# GPS.net
KiCad netlist of a schematic drawn in Altium Designer
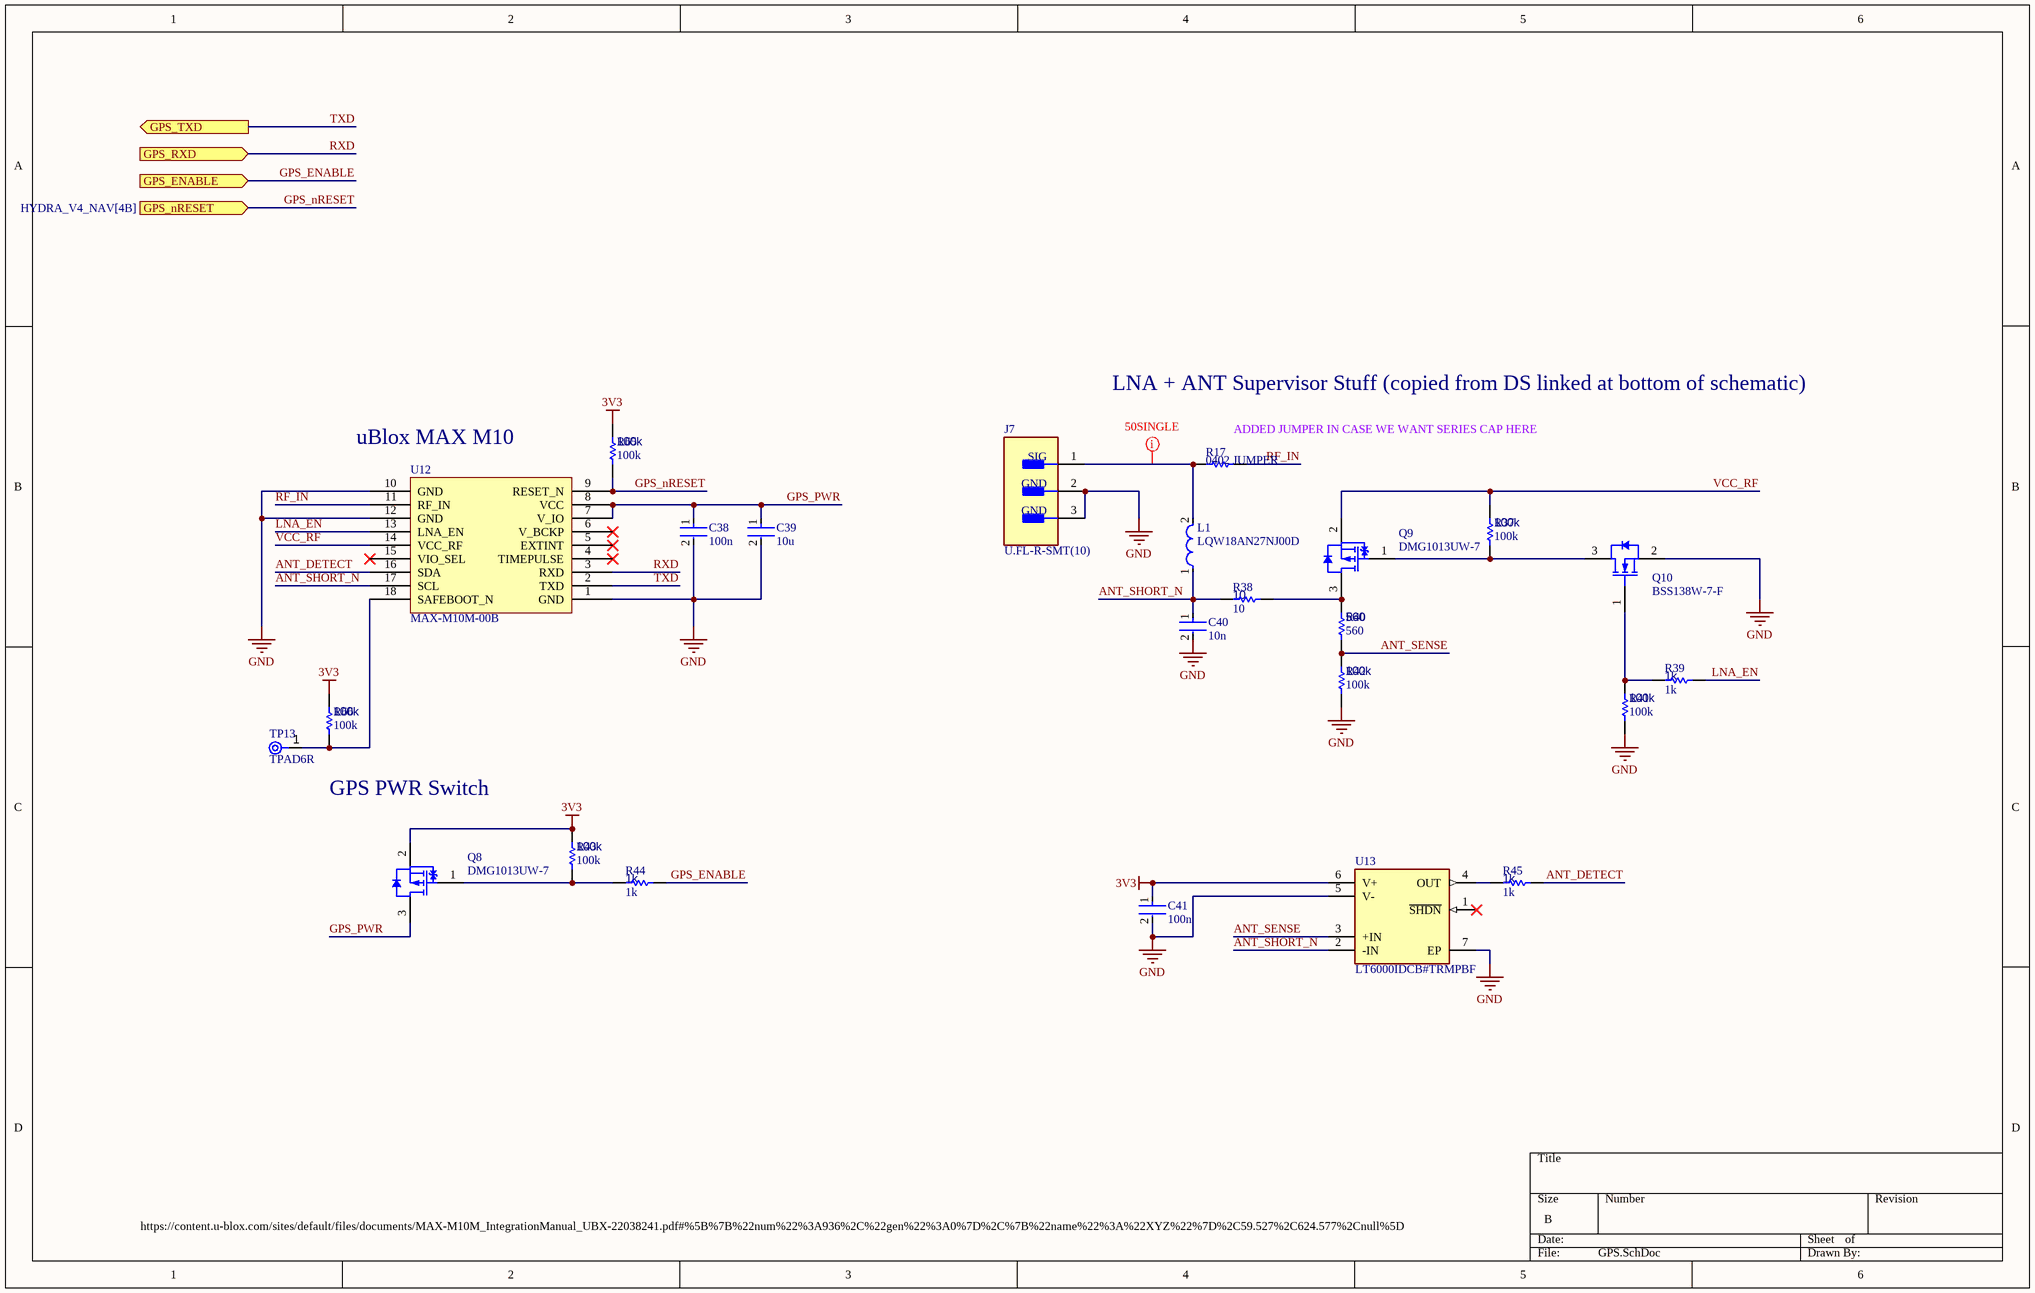
[diagram p0: GPS.SchDoc]

(export (version "E")
  (design (tool "Eeschema 10.0.6"))
  (components
    (comp (ref "C38")
      (value "100n")
      (footprint "FP-0402-L_1_0_0_05-W_0_5-IPC_A")
      (description "LARGE PADS, 0402 CAP, CHANGE COMMENT TO MATCH REAL P/N")
      (libsource (lib "Space Concordia") (part "b4654b650e69147ec39a6b967a45e02"))
    )
    (comp (ref "C39")
      (value "10u")
      (footprint "FP-0402-L_1_0_0_05-W_0_5-IPC_A")
      (description "LARGE PADS, 0402 CAP, CHANGE COMMENT TO MATCH REAL P/N")
      (libsource (lib "Space Concordia") (part "b4654b650e69147ec39a6b967a45e02"))
    )
    (comp (ref "C40")
      (value "10n")
      (footprint "FP-0402-L_1_0_0_05-W_0_5-IPC_A")
      (description "LARGE PADS, 0402 CAP, CHANGE COMMENT TO MATCH REAL P/N")
      (libsource (lib "Space Concordia") (part "b4654b650e69147ec39a6b967a45e02"))
    )
    (comp (ref "C41")
      (value "100n")
      (footprint "FP-0402-L_1_0_0_05-W_0_5-IPC_A")
      (description "LARGE PADS, 0402 CAP, CHANGE COMMENT TO MATCH REAL P/N")
      (libsource (lib "Space Concordia") (part "b4654b650e69147ec39a6b967a45e02"))
    )
    (comp (ref "J7")
      (value "U.FL-R-SMT(10)")
      (footprint "FP-U_FL-R-SMT_10-MFG")
      (description "CONN U.FL RCPT STR 50 OHM SMD")
      (libsource (lib "Altium Content Vault") (part "eef6fde44c591823e8076210edfe12f"))
    )
    (comp (ref "L1")
      (value "LQW18AN27NJ00D")
      (footprint "FP-LQW18AN_00-MFG")
      (description "Wire Wound RF Inductor 27nH ±5% 440mA 0.21Ω 0603 (1608)")
      (fields (field (name "TOLERANCE") "5%"))
      (libsource (lib "Altium Content Vault") (part "725321dda6339637d4d059423bc1c3c"))
    )
    (comp (ref "Q8")
      (value "DMG1013UW-7")
      (footprint "DIOD-SOT323-3_V")
      (fields (field (name "MANUFACTURER") "Diodes Inc"))
      (libsource (lib "Altium Content Vault") (part "PEMOS-GSD-3_C"))
    )
    (comp (ref "Q9")
      (value "DMG1013UW-7")
      (footprint "DIOD-SOT323-3_V")
      (fields (field (name "MANUFACTURER") "Diodes Inc"))
      (libsource (lib "Altium Content Vault") (part "PEMOS-GSD-3_C"))
    )
    (comp (ref "Q10")
      (value "BSS138W-7-F")
      (footprint "DIOD-SOT323-3_V")
      (fields (field (name "MANUFACTURER") "DiodesIncorporated"))
      (libsource (lib "Altium Content Vault") (part "NEMOS-GSD-3"))
    )
    (comp (ref "R17")
      (value "0402 JUMPER")
      (footprint "RESC1005X40X25ML05T05")
      (description "READ THE NAME")
      (libsource (lib "Space Concordia") (part "CMP-009-00206-2"))
    )
    (comp (ref "R37")
      (value "100k")
      (footprint "R0603B")
      (description "Resistor")
      (fields (field (name "ALTIUM_VALUE") "100k"))
      (libsource (lib "Space Concordia") (part "Resistor"))
    )
    (comp (ref "R38")
      (value "10")
      (footprint "R0603B")
      (description "Resistor")
      (fields (field (name "ALTIUM_VALUE") "10"))
      (libsource (lib "Space Concordia") (part "Resistor"))
    )
    (comp (ref "R39")
      (value "1k")
      (footprint "R0603B")
      (description "Resistor")
      (fields (field (name "ALTIUM_VALUE") "1k"))
      (libsource (lib "Space Concordia") (part "Resistor"))
    )
    (comp (ref "R40")
      (value "560")
      (footprint "R0603B")
      (description "Resistor")
      (fields (field (name "ALTIUM_VALUE") "560"))
      (libsource (lib "Space Concordia") (part "Resistor"))
    )
    (comp (ref "R41")
      (value "100k")
      (footprint "R0603B")
      (description "Resistor")
      (fields (field (name "ALTIUM_VALUE") "100k"))
      (libsource (lib "Space Concordia") (part "Resistor"))
    )
    (comp (ref "R42")
      (value "100k")
      (footprint "R0603B")
      (description "Resistor")
      (fields (field (name "ALTIUM_VALUE") "100k"))
      (libsource (lib "Space Concordia") (part "Resistor"))
    )
    (comp (ref "R43")
      (value "100k")
      (footprint "R0603B")
      (description "Resistor")
      (fields (field (name "ALTIUM_VALUE") "100k"))
      (libsource (lib "Space Concordia") (part "Resistor"))
    )
    (comp (ref "R44")
      (value "1k")
      (footprint "R0603B")
      (description "Resistor")
      (fields (field (name "ALTIUM_VALUE") "1k"))
      (libsource (lib "Space Concordia") (part "Resistor"))
    )
    (comp (ref "R45")
      (value "1k")
      (footprint "R0603B")
      (description "Resistor")
      (fields (field (name "ALTIUM_VALUE") "1k"))
      (libsource (lib "Space Concordia") (part "Resistor"))
    )
    (comp (ref "R65")
      (value "100k")
      (footprint "R0603B")
      (description "Resistor")
      (fields (field (name "ALTIUM_VALUE") "100k"))
      (libsource (lib "Space Concordia") (part "Resistor"))
    )
    (comp (ref "R66")
      (value "100k")
      (footprint "R0603B")
      (description "Resistor")
      (fields (field (name "ALTIUM_VALUE") "100k"))
      (libsource (lib "Space Concordia") (part "Resistor"))
    )
    (comp (ref "TP13")
      (value "TPAD6R")
      (footprint "New footprint 1")
      (description "Test Point .6mm")
      (libsource (lib "Space Concordia") (part "TP"))
    )
    (comp (ref "U12")
      (value "MAX-M10M-00B")
      (footprint "MAX-M10M-00B-Footprint-1")
      (description "Gnss Lcc Rx Mod, Rom, Crystal")
      (libsource (lib "Space Concordia") (part "MAX-M10M-00B"))
    )
    (comp (ref "U13")
      (value "LT6000IDCB#TRMPBF")
      (footprint "FP-DCB-6-05-08-1715-MFG")
      (description "IC OPAMP GP 1 CIRCUIT 6DFN")
      (libsource (lib "Altium Content Vault") (part "33bb285994f2e703f79bf9d86341a8a"))
    )
  )
  (nets
    (net (code "1") (name "/ANT_DETECT") (class "Default")
      (node (ref "R45") (pin "2") (pinfunction "2_2") (pintype "passive"))
      (node (ref "U12") (pin "16") (pinfunction "SDA_16") (pintype "passive"))
    )
    (net (code "2") (name "/ANT_SENSE") (class "Default")
      (node (ref "R40") (pin "2") (pinfunction "2_2") (pintype "passive"))
      (node (ref "R42") (pin "1") (pinfunction "1_1") (pintype "passive"))
      (node (ref "U13") (pin "3") (pinfunction "+IN_3") (pintype "tri_state"))
    )
    (net (code "3") (name "/ANT_SHORT_N") (class "Default")
      (node (ref "C40") (pin "1") (pinfunction "1_1") (pintype "passive"))
      (node (ref "L1") (pin "1") (pinfunction "1_1") (pintype "passive"))
      (node (ref "R38") (pin "1") (pinfunction "1_1") (pintype "passive"))
      (node (ref "U12") (pin "17") (pinfunction "SCL_17") (pintype "passive"))
      (node (ref "U13") (pin "2") (pinfunction "-IN_2") (pintype "tri_state"))
    )
    (net (code "4") (name "/GPS_ENABLE") (class "Default")
      (node (ref "R44") (pin "2") (pinfunction "2_2") (pintype "passive"))
    )
    (net (code "5") (name "/GPS_PWR") (class "Default")
      (node (ref "C38") (pin "1") (pinfunction "1_1") (pintype "passive"))
      (node (ref "C39") (pin "1") (pinfunction "1_1") (pintype "passive"))
      (node (ref "Q8") (pin "3") (pinfunction "D_3") (pintype "passive"))
      (node (ref "U12") (pin "7") (pinfunction "V_IO_7") (pintype "passive"))
      (node (ref "U12") (pin "8") (pinfunction "VCC_8") (pintype "passive"))
    )
    (net (code "6") (name "/GPS_nRESET") (class "Default")
      (node (ref "R65") (pin "2") (pinfunction "2_2") (pintype "passive"))
      (node (ref "U12") (pin "9") (pinfunction "RESET_N_9") (pintype "passive"))
    )
    (net (code "7") (name "/LNA_EN") (class "Default")
      (node (ref "R39") (pin "2") (pinfunction "2_2") (pintype "passive"))
      (node (ref "U12") (pin "13") (pinfunction "LNA_EN_13") (pintype "passive"))
    )
    (net (code "8") (name "/RF_IN") (class "Default")
      (node (ref "R17") (pin "2") (pinfunction "2_2") (pintype "passive"))
      (node (ref "U12") (pin "11") (pinfunction "RF_IN_11") (pintype "passive"))
    )
    (net (code "9") (name "/RXD") (class "Default")
      (node (ref "U12") (pin "3") (pinfunction "RXD_3") (pintype "passive"))
    )
    (net (code "10") (name "/TXD") (class "Default")
      (node (ref "U12") (pin "2") (pinfunction "TXD_2") (pintype "passive"))
    )
    (net (code "11") (name "/VCC_RF") (class "Default")
      (node (ref "Q9") (pin "2") (pinfunction "S_2") (pintype "passive"))
      (node (ref "R37") (pin "1") (pinfunction "1_1") (pintype "passive"))
      (node (ref "U12") (pin "14") (pinfunction "VCC_RF_14") (pintype "passive"))
    )
    (net (code "12") (name "3V3") (class "Default")
      (node (ref "C41") (pin "1") (pinfunction "1_1") (pintype "passive"))
      (node (ref "Q8") (pin "2") (pinfunction "S_2") (pintype "passive"))
      (node (ref "R43") (pin "1") (pinfunction "1_1") (pintype "passive"))
      (node (ref "R65") (pin "1") (pinfunction "1_1") (pintype "passive"))
      (node (ref "R66") (pin "1") (pinfunction "1_1") (pintype "passive"))
      (node (ref "U13") (pin "6") (pinfunction "V+_6") (pintype "power_in"))
    )
    (net (code "13") (name "GND") (class "Default")
      (node (ref "C38") (pin "2") (pinfunction "2_2") (pintype "passive"))
      (node (ref "C39") (pin "2") (pinfunction "2_2") (pintype "passive"))
      (node (ref "C40") (pin "2") (pinfunction "2_2") (pintype "passive"))
      (node (ref "C41") (pin "2") (pinfunction "2_2") (pintype "passive"))
      (node (ref "J7") (pin "2") (pinfunction "GND_2") (pintype "power_in"))
      (node (ref "J7") (pin "3") (pinfunction "GND_3") (pintype "power_in"))
      (node (ref "Q10") (pin "2") (pinfunction "S_2") (pintype "passive"))
      (node (ref "R41") (pin "2") (pinfunction "2_2") (pintype "passive"))
      (node (ref "R42") (pin "2") (pinfunction "2_2") (pintype "passive"))
      (node (ref "U12") (pin "1") (pinfunction "GND_1") (pintype "passive"))
      (node (ref "U12") (pin "10") (pinfunction "GND_10") (pintype "passive"))
      (node (ref "U12") (pin "12") (pinfunction "GND_12") (pintype "passive"))
      (node (ref "U13") (pin "5") (pinfunction "V-_5") (pintype "power_in"))
      (node (ref "U13") (pin "7") (pinfunction "EP_7") (pintype "power_in"))
    )
    (net (code "14") (name "Net-(J7-SIG)") (class "Default")
      (node (ref "J7") (pin "1") (pinfunction "SIG_1") (pintype "passive"))
      (node (ref "L1") (pin "2") (pinfunction "2_2") (pintype "passive"))
      (node (ref "R17") (pin "1") (pinfunction "1_1") (pintype "passive"))
    )
    (net (code "15") (name "Net-(Q8-G)") (class "Default")
      (node (ref "Q8") (pin "1") (pinfunction "G_1") (pintype "passive"))
      (node (ref "R43") (pin "2") (pinfunction "2_2") (pintype "passive"))
      (node (ref "R44") (pin "1") (pinfunction "1_1") (pintype "passive"))
    )
    (net (code "16") (name "Net-(Q9-D)") (class "Default")
      (node (ref "Q9") (pin "3") (pinfunction "D_3") (pintype "passive"))
      (node (ref "R38") (pin "2") (pinfunction "2_2") (pintype "passive"))
      (node (ref "R40") (pin "1") (pinfunction "1_1") (pintype "passive"))
    )
    (net (code "17") (name "Net-(Q10-D)") (class "Default")
      (node (ref "Q10") (pin "3") (pinfunction "D_3") (pintype "passive"))
      (node (ref "Q9") (pin "1") (pinfunction "G_1") (pintype "passive"))
      (node (ref "R37") (pin "2") (pinfunction "2_2") (pintype "passive"))
    )
    (net (code "18") (name "Net-(Q10-G)") (class "Default")
      (node (ref "Q10") (pin "1") (pinfunction "G_1") (pintype "passive"))
      (node (ref "R39") (pin "1") (pinfunction "1_1") (pintype "passive"))
      (node (ref "R41") (pin "1") (pinfunction "1_1") (pintype "passive"))
    )
    (net (code "19") (name "Net-(TP13-TP)") (class "Default")
      (node (ref "R66") (pin "2") (pinfunction "2_2") (pintype "passive"))
      (node (ref "TP13") (pin "1") (pinfunction "TP_1") (pintype "passive"))
      (node (ref "U12") (pin "18") (pinfunction "SAFEBOOT_N_18") (pintype "passive"))
    )
    (net (code "20") (name "Net-(U13-OUT)") (class "Default")
      (node (ref "R45") (pin "1") (pinfunction "1_1") (pintype "passive"))
      (node (ref "U13") (pin "4") (pinfunction "OUT_4") (pintype "output"))
    )
    (net (code "21") (name "unconnected-(U12-EXTINT-Pad5)") (class "Default")
      (node (ref "U12") (pin "5") (pinfunction "EXTINT_5") (pintype "passive+no_connect"))
    )
    (net (code "22") (name "unconnected-(U12-TIMEPULSE-Pad4)") (class "Default")
      (node (ref "U12") (pin "4") (pinfunction "TIMEPULSE_4") (pintype "passive+no_connect"))
    )
    (net (code "23") (name "unconnected-(U12-VIO_SEL-Pad15)") (class "Default")
      (node (ref "U12") (pin "15") (pinfunction "VIO_SEL_15") (pintype "passive+no_connect"))
    )
    (net (code "24") (name "unconnected-(U12-V_BCKP-Pad6)") (class "Default")
      (node (ref "U12") (pin "6") (pinfunction "V_BCKP_6") (pintype "passive+no_connect"))
    )
    (net (code "25") (name "unconnected-(U13-~{SHDN}-Pad1)") (class "Default")
      (node (ref "U13") (pin "1") (pinfunction "~{SHDN}_1") (pintype "input+no_connect"))
    )
  )
)
